# esquemotor.net
KiCad netlist of a schematic drawn in EAGLE
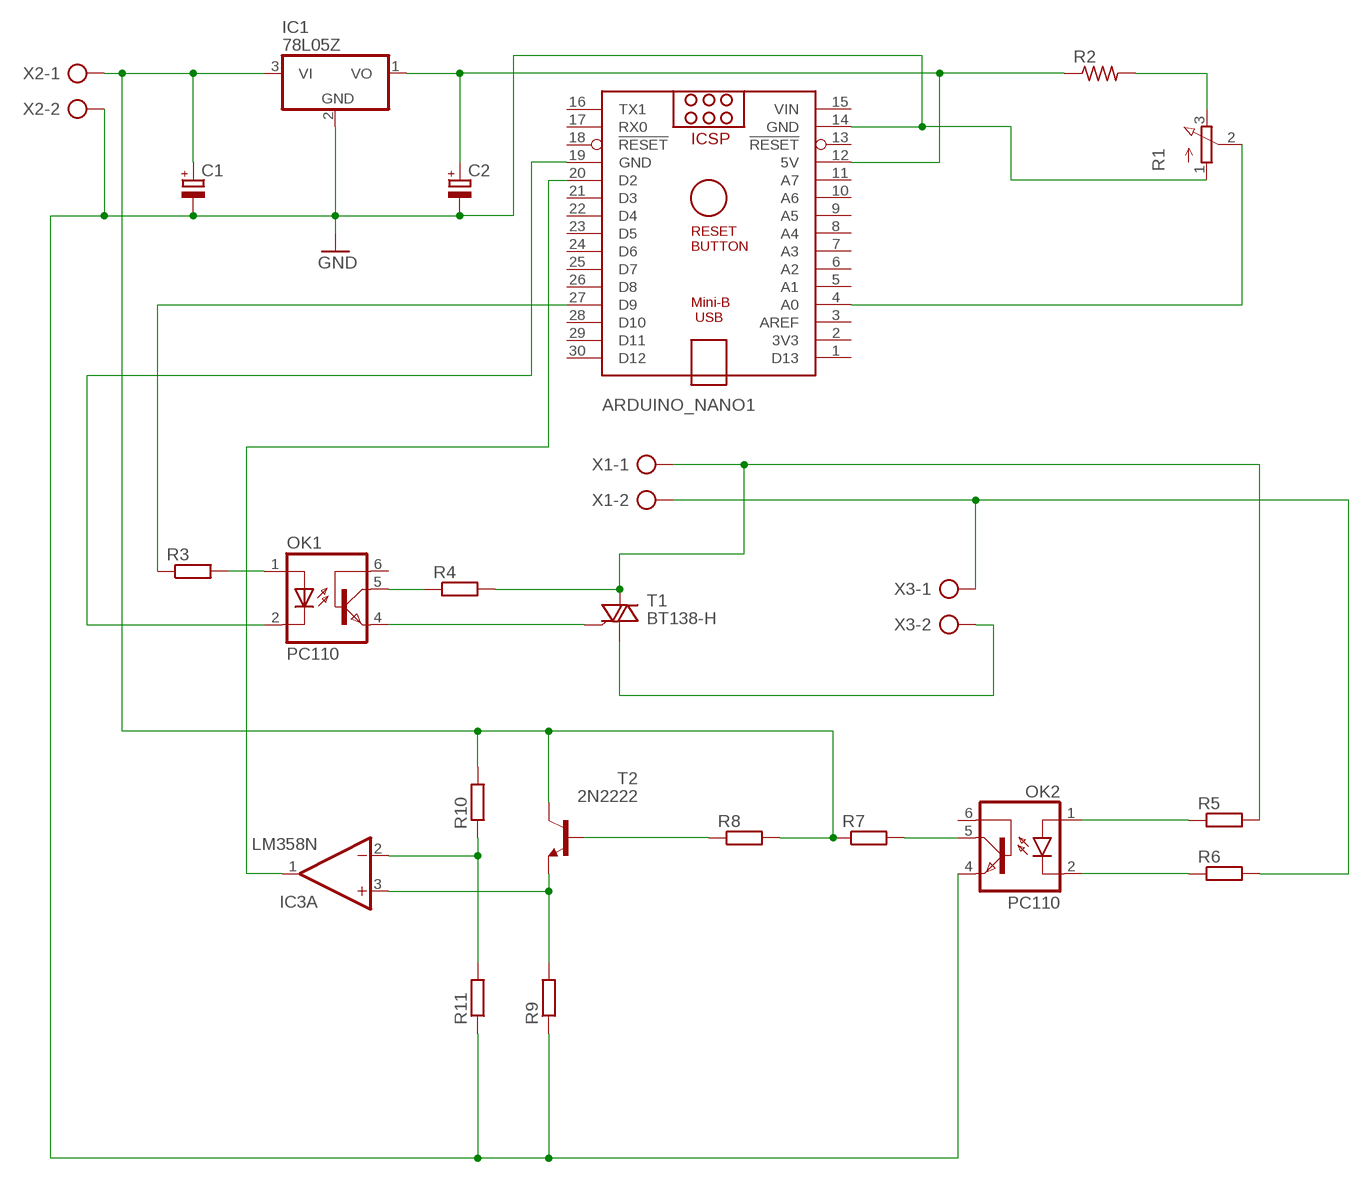
[diagram p0: schematic, sheet 1]

(export (version "E")
  (design (tool "Eeschema 10.0.6"))
  (components
    (comp (ref "ARDUINO_NANO1")
      (value "ARDUINO_NANO")
      (footprint "eagle-import:ARDUINO_NANO")
      (libsource (lib "eagle-import") (part "ARDUINO_NANO"))
    )
    (comp (ref "C1")
      (value "CPOL-EUE7.5-16")
      (footprint "eagle-import:E7,5-16")
      (libsource (lib "eagle-import") (part "CPOL-EUE7.5-16"))
    )
    (comp (ref "C2")
      (value "CPOL-EUE7.5-16")
      (footprint "eagle-import:E7,5-16")
      (libsource (lib "eagle-import") (part "CPOL-EUE7.5-16"))
    )
    (comp (ref "IC1")
      (value "78L05Z")
      (footprint "eagle-import:TO92")
      (libsource (lib "eagle-import") (part "78ZL05"))
    )
    (comp (ref "IC3")
      (value "LM358N")
      (footprint "eagle-import:DIL08")
      (libsource (lib "eagle-import") (part "LM358N"))
    )
    (comp (ref "OK1")
      (value "PC110")
      (footprint "eagle-import:DIL06")
      (libsource (lib "eagle-import") (part "PC110"))
    )
    (comp (ref "OK2")
      (value "PC110")
      (footprint "eagle-import:DIL06")
      (libsource (lib "eagle-import") (part "optocoupler_320_PC110"))
    )
    (comp (ref "R1")
      (value "3RP/1610N")
      (footprint "eagle-import:3RP_1610N")
      (libsource (lib "eagle-import") (part "3RP/1610N"))
    )
    (comp (ref "R2")
      (value "R-US_0207/5V")
      (footprint "eagle-import:0207_5V")
      (libsource (lib "eagle-import") (part "R-US_0207/5V"))
    )
    (comp (ref "R3")
      (value "R-EU_0207/7")
      (footprint "eagle-import:0207_7")
      (libsource (lib "eagle-import") (part "R-EU_0207/7"))
    )
    (comp (ref "R4")
      (value "R-EU_0207/7")
      (footprint "eagle-import:0207_7")
      (libsource (lib "eagle-import") (part "R-EU_0207/7"))
    )
    (comp (ref "R5")
      (value "R-EU_0207/5V")
      (footprint "eagle-import:0207_5V")
      (libsource (lib "eagle-import") (part "R-EU_0207/5V"))
    )
    (comp (ref "R6")
      (value "R-EU_0207/5V")
      (footprint "eagle-import:0207_5V")
      (libsource (lib "eagle-import") (part "R-EU_0207/5V"))
    )
    (comp (ref "R7")
      (value "R-EU_0207/7")
      (footprint "eagle-import:0207_7")
      (libsource (lib "eagle-import") (part "R-EU_0207/7"))
    )
    (comp (ref "R8")
      (value "R-EU_0207/7")
      (footprint "eagle-import:0207_7")
      (libsource (lib "eagle-import") (part "R-EU_0207/7"))
    )
    (comp (ref "R9")
      (value "R-EU_0207/7")
      (footprint "eagle-import:0207_7")
      (libsource (lib "eagle-import") (part "R-EU_0207/7"))
    )
    (comp (ref "R10")
      (value "R-EU_0207/7")
      (footprint "eagle-import:0207_7")
      (libsource (lib "eagle-import") (part "R-EU_0207/7"))
    )
    (comp (ref "R11")
      (value "R-EU_0207/7")
      (footprint "eagle-import:0207_7")
      (libsource (lib "eagle-import") (part "R-EU_0207/7"))
    )
    (comp (ref "T1")
      (value "BT138-H")
      (footprint "eagle-import:TO220BH")
      (libsource (lib "eagle-import") (part "BT138-H"))
    )
    (comp (ref "T2")
      (value "2N2222")
      (footprint "eagle-import:TO18")
      (libsource (lib "eagle-import") (part "2N2222"))
    )
    (comp (ref "X1")
      (value "AK500/2-H")
      (footprint "eagle-import:AK500_2-H")
      (libsource (lib "eagle-import") (part "AK500/2-H"))
    )
    (comp (ref "X2")
      (value "AK500/2-H")
      (footprint "eagle-import:AK500_2-H")
      (libsource (lib "eagle-import") (part "AK500/2-H"))
    )
    (comp (ref "X3")
      (value "AK500/2-H")
      (footprint "eagle-import:AK500_2-H")
      (libsource (lib "eagle-import") (part "AK500/2-H"))
    )
  )
  (nets
    (net (code "1") (name "/VIN") (class "Default")
      (node (ref "ARDUINO_NANO1") (pin "15") (pinfunction "VIN_15") (pintype "power_in"))
    )
    (net (code "2") (name "GND") (class "Default")
      (node (ref "ARDUINO_NANO1") (pin "14") (pinfunction "GND_14") (pintype "power_in"))
      (node (ref "C1") (pin "-") (pinfunction "-_-") (pintype "passive"))
      (node (ref "C2") (pin "-") (pinfunction "-_-") (pintype "passive"))
      (node (ref "IC1") (pin "2") (pinfunction "GND_2") (pintype "passive"))
      (node (ref "OK2") (pin "4") (pinfunction "EMI_4") (pintype "passive"))
      (node (ref "R1") (pin "1") (pinfunction "A_1") (pintype "passive"))
      (node (ref "R11") (pin "1") (pinfunction "1_1") (pintype "passive"))
      (node (ref "R9") (pin "1") (pinfunction "1_1") (pintype "passive"))
      (node (ref "X2") (pin "2") (pinfunction "KL_2") (pintype "passive"))
    )
    (net (code "3") (name "Net-(ARDUINO_NANO1-5V)") (class "Default")
      (node (ref "ARDUINO_NANO1") (pin "12") (pinfunction "5V_12") (pintype "power_in"))
      (node (ref "C2") (pin "+") (pinfunction "+_+") (pintype "passive"))
      (node (ref "IC1") (pin "1") (pinfunction "VO_1") (pintype "passive"))
      (node (ref "R2") (pin "1") (pinfunction "1_1") (pintype "passive"))
    )
    (net (code "4") (name "Net-(ARDUINO_NANO1-A0)") (class "Default")
      (node (ref "ARDUINO_NANO1") (pin "4") (pinfunction "A0_4") (pintype "bidirectional"))
      (node (ref "R1") (pin "2") (pinfunction "S_2") (pintype "passive"))
    )
    (net (code "5") (name "Net-(ARDUINO_NANO1-D2)") (class "Default")
      (node (ref "ARDUINO_NANO1") (pin "20") (pinfunction "D2_20") (pintype "bidirectional"))
      (node (ref "IC3") (pin "1") (pinfunction "OUT_1") (pintype "output"))
    )
    (net (code "6") (name "Net-(ARDUINO_NANO1-D9)") (class "Default")
      (node (ref "ARDUINO_NANO1") (pin "27") (pinfunction "D9_27") (pintype "bidirectional"))
      (node (ref "R3") (pin "1") (pinfunction "1_1") (pintype "passive"))
    )
    (net (code "7") (name "Net-(IC1-VI)") (class "Default")
      (node (ref "C1") (pin "+") (pinfunction "+_+") (pintype "passive"))
      (node (ref "IC1") (pin "3") (pinfunction "VI_3") (pintype "input"))
      (node (ref "R10") (pin "2") (pinfunction "2_2") (pintype "passive"))
      (node (ref "R7") (pin "1") (pinfunction "1_1") (pintype "passive"))
      (node (ref "R8") (pin "2") (pinfunction "2_2") (pintype "passive"))
      (node (ref "T2") (pin "3") (pinfunction "C_3") (pintype "passive"))
      (node (ref "X2") (pin "1") (pinfunction "KL_1") (pintype "passive"))
    )
    (net (code "8") (name "Net-(IC3A-+IN)") (class "Default")
      (node (ref "IC3") (pin "3") (pinfunction "+IN_3") (pintype "input"))
      (node (ref "R9") (pin "2") (pinfunction "2_2") (pintype "passive"))
      (node (ref "T2") (pin "1") (pinfunction "E_1") (pintype "passive"))
    )
    (net (code "9") (name "Net-(IC3A--IN)") (class "Default")
      (node (ref "IC3") (pin "2") (pinfunction "-IN_2") (pintype "input"))
      (node (ref "R10") (pin "1") (pinfunction "1_1") (pintype "passive"))
      (node (ref "R11") (pin "2") (pinfunction "2_2") (pintype "passive"))
    )
    (net (code "10") (name "Net-(OK1-A)") (class "Default")
      (node (ref "OK1") (pin "1") (pinfunction "A_1") (pintype "passive"))
      (node (ref "R3") (pin "2") (pinfunction "2_2") (pintype "passive"))
    )
    (net (code "11") (name "Net-(OK1-C)") (class "Default")
      (node (ref "ARDUINO_NANO1") (pin "19") (pinfunction "GND_19") (pintype "power_in"))
      (node (ref "OK1") (pin "2") (pinfunction "C_2") (pintype "passive"))
    )
    (net (code "12") (name "Net-(OK1-COL)") (class "Default")
      (node (ref "OK1") (pin "5") (pinfunction "COL_5") (pintype "passive"))
      (node (ref "R4") (pin "1") (pinfunction "1_1") (pintype "passive"))
    )
    (net (code "13") (name "Net-(OK1-EMI)") (class "Default")
      (node (ref "OK1") (pin "4") (pinfunction "EMI_4") (pintype "passive"))
      (node (ref "T1") (pin "G") (pinfunction "G_G") (pintype "passive"))
    )
    (net (code "14") (name "Net-(OK2-A)") (class "Default")
      (node (ref "OK2") (pin "1") (pinfunction "A_1") (pintype "passive"))
      (node (ref "R5") (pin "1") (pinfunction "1_1") (pintype "passive"))
    )
    (net (code "15") (name "Net-(OK2-C)") (class "Default")
      (node (ref "OK2") (pin "2") (pinfunction "C_2") (pintype "passive"))
      (node (ref "R6") (pin "1") (pinfunction "1_1") (pintype "passive"))
    )
    (net (code "16") (name "Net-(OK2-COL)") (class "Default")
      (node (ref "OK2") (pin "5") (pinfunction "COL_5") (pintype "passive"))
      (node (ref "R7") (pin "2") (pinfunction "2_2") (pintype "passive"))
    )
    (net (code "17") (name "Net-(R1-E)") (class "Default")
      (node (ref "R1") (pin "3") (pinfunction "E_3") (pintype "passive"))
      (node (ref "R2") (pin "2") (pinfunction "2_2") (pintype "passive"))
    )
    (net (code "18") (name "Net-(T1-A1)") (class "Default")
      (node (ref "T1") (pin "T1") (pinfunction "A1_T1") (pintype "passive"))
      (node (ref "X3") (pin "2") (pinfunction "KL_2") (pintype "passive"))
    )
    (net (code "19") (name "Net-(T1-A2)") (class "Default")
      (node (ref "R4") (pin "2") (pinfunction "2_2") (pintype "passive"))
      (node (ref "R5") (pin "2") (pinfunction "2_2") (pintype "passive"))
      (node (ref "T1") (pin "T2") (pinfunction "A2_T2") (pintype "passive"))
      (node (ref "X1") (pin "1") (pinfunction "KL_1") (pintype "passive"))
    )
    (net (code "20") (name "Net-(T2-B)") (class "Default")
      (node (ref "R8") (pin "1") (pinfunction "1_1") (pintype "passive"))
      (node (ref "T2") (pin "2") (pinfunction "B_2") (pintype "passive"))
    )
    (net (code "21") (name "Net-(X1B-KL)") (class "Default")
      (node (ref "R6") (pin "2") (pinfunction "2_2") (pintype "passive"))
      (node (ref "X1") (pin "2") (pinfunction "KL_2") (pintype "passive"))
      (node (ref "X3") (pin "1") (pinfunction "KL_1") (pintype "passive"))
    )
    (net (code "22") (name "unconnected-(ARDUINO_NANO1-3V3-Pad2)") (class "Default")
      (node (ref "ARDUINO_NANO1") (pin "2") (pinfunction "3V3_2") (pintype "output"))
    )
    (net (code "23") (name "unconnected-(ARDUINO_NANO1-A1-Pad5)") (class "Default")
      (node (ref "ARDUINO_NANO1") (pin "5") (pinfunction "A1_5") (pintype "bidirectional"))
    )
    (net (code "24") (name "unconnected-(ARDUINO_NANO1-A2-Pad6)") (class "Default")
      (node (ref "ARDUINO_NANO1") (pin "6") (pinfunction "A2_6") (pintype "bidirectional"))
    )
    (net (code "25") (name "unconnected-(ARDUINO_NANO1-A3-Pad7)") (class "Default")
      (node (ref "ARDUINO_NANO1") (pin "7") (pinfunction "A3_7") (pintype "bidirectional"))
    )
    (net (code "26") (name "unconnected-(ARDUINO_NANO1-A4-Pad8)") (class "Default")
      (node (ref "ARDUINO_NANO1") (pin "8") (pinfunction "A4_8") (pintype "bidirectional"))
    )
    (net (code "27") (name "unconnected-(ARDUINO_NANO1-A5-Pad9)") (class "Default")
      (node (ref "ARDUINO_NANO1") (pin "9") (pinfunction "A5_9") (pintype "bidirectional"))
    )
    (net (code "28") (name "unconnected-(ARDUINO_NANO1-A6-Pad10)") (class "Default")
      (node (ref "ARDUINO_NANO1") (pin "10") (pinfunction "A6_10") (pintype "bidirectional"))
    )
    (net (code "29") (name "unconnected-(ARDUINO_NANO1-A7-Pad11)") (class "Default")
      (node (ref "ARDUINO_NANO1") (pin "11") (pinfunction "A7_11") (pintype "bidirectional"))
    )
    (net (code "30") (name "unconnected-(ARDUINO_NANO1-AREF-Pad3)") (class "Default")
      (node (ref "ARDUINO_NANO1") (pin "3") (pinfunction "AREF_3") (pintype "input"))
    )
    (net (code "31") (name "unconnected-(ARDUINO_NANO1-D3-Pad21)") (class "Default")
      (node (ref "ARDUINO_NANO1") (pin "21") (pinfunction "D3_21") (pintype "bidirectional"))
    )
    (net (code "32") (name "unconnected-(ARDUINO_NANO1-D4-Pad22)") (class "Default")
      (node (ref "ARDUINO_NANO1") (pin "22") (pinfunction "D4_22") (pintype "bidirectional"))
    )
    (net (code "33") (name "unconnected-(ARDUINO_NANO1-D5-Pad23)") (class "Default")
      (node (ref "ARDUINO_NANO1") (pin "23") (pinfunction "D5_23") (pintype "bidirectional"))
    )
    (net (code "34") (name "unconnected-(ARDUINO_NANO1-D6-Pad24)") (class "Default")
      (node (ref "ARDUINO_NANO1") (pin "24") (pinfunction "D6_24") (pintype "bidirectional"))
    )
    (net (code "35") (name "unconnected-(ARDUINO_NANO1-D7-Pad25)") (class "Default")
      (node (ref "ARDUINO_NANO1") (pin "25") (pinfunction "D7_25") (pintype "bidirectional"))
    )
    (net (code "36") (name "unconnected-(ARDUINO_NANO1-D8-Pad26)") (class "Default")
      (node (ref "ARDUINO_NANO1") (pin "26") (pinfunction "D8_26") (pintype "bidirectional"))
    )
    (net (code "37") (name "unconnected-(ARDUINO_NANO1-D10-Pad28)") (class "Default")
      (node (ref "ARDUINO_NANO1") (pin "28") (pinfunction "D10_28") (pintype "bidirectional"))
    )
    (net (code "38") (name "unconnected-(ARDUINO_NANO1-D11-Pad29)") (class "Default")
      (node (ref "ARDUINO_NANO1") (pin "29") (pinfunction "D11_29") (pintype "bidirectional"))
    )
    (net (code "39") (name "unconnected-(ARDUINO_NANO1-D12-Pad30)") (class "Default")
      (node (ref "ARDUINO_NANO1") (pin "30") (pinfunction "D12_30") (pintype "bidirectional"))
    )
    (net (code "40") (name "unconnected-(ARDUINO_NANO1-D13-Pad1)") (class "Default")
      (node (ref "ARDUINO_NANO1") (pin "1") (pinfunction "D13_1") (pintype "bidirectional"))
    )
    (net (code "41") (name "unconnected-(ARDUINO_NANO1-RX0-Pad17)") (class "Default")
      (node (ref "ARDUINO_NANO1") (pin "17") (pinfunction "RX0_17") (pintype "bidirectional"))
    )
    (net (code "42") (name "unconnected-(ARDUINO_NANO1-TX1-Pad16)") (class "Default")
      (node (ref "ARDUINO_NANO1") (pin "16") (pinfunction "TX1_16") (pintype "bidirectional"))
    )
    (net (code "43") (name "unconnected-(ARDUINO_NANO1-~{RESET}-Pad13)") (class "Default")
      (node (ref "ARDUINO_NANO1") (pin "13") (pinfunction "~{RESET}_13") (pintype "input"))
    )
    (net (code "44") (name "unconnected-(ARDUINO_NANO1-~{RESET}-Pad18)") (class "Default")
      (node (ref "ARDUINO_NANO1") (pin "18") (pinfunction "~{RESET}_18") (pintype "input"))
    )
    (net (code "45") (name "unconnected-(OK1-BAS-Pad6)") (class "Default")
      (node (ref "OK1") (pin "6") (pinfunction "BAS_6") (pintype "passive"))
    )
    (net (code "46") (name "unconnected-(OK2-BAS-Pad6)") (class "Default")
      (node (ref "OK2") (pin "6") (pinfunction "BAS_6") (pintype "passive"))
    )
  )
)
